# Supply.net
KiCad netlist of a schematic drawn in Altium Designer
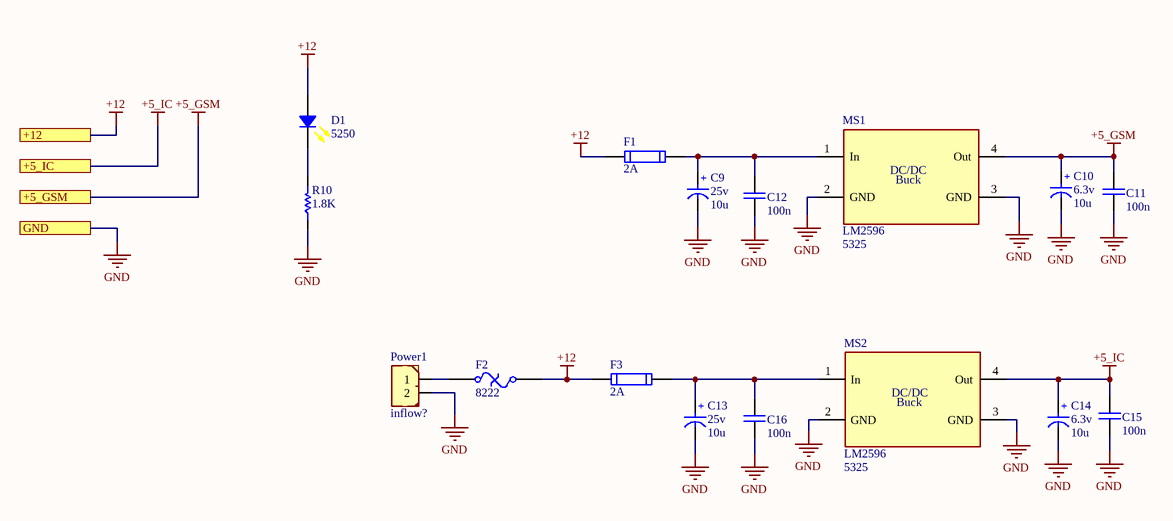
[diagram p0: Supply.SchDoc]

(export (version "E")
  (design (tool "Eeschema 10.0.6"))
  (components
    (comp (ref "C9")
      (value "10u")
      (footprint "SMT_C_Tantalum_B")
      (description "Tantalum Capacitor,TAJ Series-SMD")
      (fields (field (name "RATING") "25v") (field (name "VALIDATION") "Valid"))
      (libsource (lib "aKaReZa") (part "Cap_Tantalum"))
    )
    (comp (ref "C10")
      (value "10u")
      (footprint "SMT_C_Tantalum_B")
      (description "Tantalum Capacitor,TAJ Series-SMD")
      (fields (field (name "RATING") "6.3v") (field (name "VALIDATION") "Valid"))
      (libsource (lib "aKaReZa") (part "Cap_Tantalum"))
    )
    (comp (ref "C11")
      (value "100n")
      (footprint "CAP 1206/3216")
      (description "Bipolar ceramic capacitor SMD")
      (fields (field (name "VALIDATION") "Valid"))
      (libsource (lib "aKaReZa") (part "Cap_Multi_SMD_100nF_1206"))
    )
    (comp (ref "C12")
      (value "100n")
      (footprint "CAP 1206/3216")
      (description "Bipolar ceramic capacitor SMD")
      (fields (field (name "VALIDATION") "Valid"))
      (libsource (lib "aKaReZa") (part "Cap_Multi_SMD_100nF_1206"))
    )
    (comp (ref "C13")
      (value "10u")
      (footprint "SMT_C_Tantalum_B")
      (description "Tantalum Capacitor,TAJ Series-SMD")
      (fields (field (name "RATING") "25v") (field (name "VALIDATION") "Valid"))
      (libsource (lib "aKaReZa") (part "Cap_Tantalum"))
    )
    (comp (ref "C14")
      (value "10u")
      (footprint "SMT_C_Tantalum_B")
      (description "Tantalum Capacitor,TAJ Series-SMD")
      (fields (field (name "RATING") "6.3v") (field (name "VALIDATION") "Valid"))
      (libsource (lib "aKaReZa") (part "Cap_Tantalum"))
    )
    (comp (ref "C15")
      (value "100n")
      (footprint "CAP 1206/3216")
      (description "Bipolar ceramic capacitor SMD")
      (fields (field (name "VALIDATION") "Valid"))
      (libsource (lib "aKaReZa") (part "Cap_Multi_SMD_100nF_1206"))
    )
    (comp (ref "C16")
      (value "100n")
      (footprint "CAP 1206/3216")
      (description "Bipolar ceramic capacitor SMD")
      (fields (field (name "VALIDATION") "Valid"))
      (libsource (lib "aKaReZa") (part "Cap_Multi_SMD_100nF_1206"))
    )
    (comp (ref "D1")
      (value "Yellow, 1206")
      (footprint "LED 1206/3216 YELLOW")
      (description "LED")
      (fields (field (name "INFLOW") "5250") (field (name "VALIDATION") "Valid"))
      (libsource (lib "aKaReZa") (part "Semi_LED_Yellow_1206"))
    )
    (comp (ref "F1")
      (value "2A")
      (footprint "1206_F")
      (description "Short circiut  protection")
      (fields (field (name "VALIDATION") "Valid"))
      (libsource (lib "aKaReZa") (part "Other_Elec_Fuse_SMD"))
    )
    (comp (ref "F2")
      (value "180'C, 10'A")
      (footprint "PIN-W2/E2.8")
      (description "Thermal Fuse")
      (fields (field (name "INFLOW") "8222") (field (name "VALIDATION") "NT"))
      (libsource (lib "aKaReZa") (part "Other_Elec_Fuse_Thermal"))
    )
    (comp (ref "F3")
      (value "2A")
      (footprint "1206_F")
      (description "Short circiut  protection")
      (fields (field (name "VALIDATION") "Valid"))
      (libsource (lib "aKaReZa") (part "Other_Elec_Fuse_SMD"))
    )
    (comp (ref "MS1")
      (value "LM2596")
      (footprint "LM2596_modsen")
      (description "DC to DC Buck converter 1.23V-30V 3A")
      (fields (field (name "INFLOW") "5325") (field (name "VALIDATION") "Valid"))
      (libsource (lib "aKaReZa") (part "ModSen_LM2596"))
    )
    (comp (ref "MS2")
      (value "LM2596")
      (footprint "LM2596_modsen")
      (description "DC to DC Buck converter 1.23V-30V 3A")
      (fields (field (name "INFLOW") "5325") (field (name "VALIDATION") "Valid"))
      (libsource (lib "aKaReZa") (part "ModSen_LM2596"))
    )
    (comp (ref "Power1")
      (value "2'Pin")
      (footprint "Phoenix_2PIN_RA_P5.08mm")
      (description "Power Connector 2'Pin")
      (fields (field (name "INFLOW") "inflow?") (field (name "VALIDATION") "NT"))
      (libsource (lib "aKaReZa") (part "Con_Power_2"))
    )
    (comp (ref "R10")
      (value "1.8K")
      (footprint "RES 1206 (3216X08L)")
      (description "Resistor")
      (fields (field (name "VALIDATION") "Valid"))
      (libsource (lib "aKaReZa") (part "Res_SMD_1206"))
    )
  )
  (nets
    (net (code "1") (name "+5_GSM") (class "Default")
      (node (ref "C10") (pin "1") (pinfunction "+_1") (pintype "passive"))
      (node (ref "C11") (pin "1") (pinfunction "1_1") (pintype "passive"))
      (node (ref "MS1") (pin "4") (pinfunction "Out_4") (pintype "power_in"))
    )
    (net (code "2") (name "+5_IC") (class "Default")
      (node (ref "C14") (pin "1") (pinfunction "+_1") (pintype "passive"))
      (node (ref "C15") (pin "1") (pinfunction "1_1") (pintype "passive"))
      (node (ref "MS2") (pin "4") (pinfunction "Out_4") (pintype "power_in"))
    )
    (net (code "3") (name "+12") (class "Default")
      (node (ref "D1") (pin "1") (pinfunction "1_1") (pintype "passive"))
      (node (ref "F1") (pin "1") (pinfunction "1_1") (pintype "passive"))
      (node (ref "F2") (pin "2") (pinfunction "2_2") (pintype "passive"))
      (node (ref "F3") (pin "1") (pinfunction "1_1") (pintype "passive"))
    )
    (net (code "4") (name "GND") (class "Default")
      (node (ref "C10") (pin "2") (pinfunction "-_2") (pintype "passive"))
      (node (ref "C11") (pin "2") (pinfunction "2_2") (pintype "passive"))
      (node (ref "C12") (pin "2") (pinfunction "2_2") (pintype "passive"))
      (node (ref "C13") (pin "2") (pinfunction "-_2") (pintype "passive"))
      (node (ref "C14") (pin "2") (pinfunction "-_2") (pintype "passive"))
      (node (ref "C15") (pin "2") (pinfunction "2_2") (pintype "passive"))
      (node (ref "C16") (pin "2") (pinfunction "2_2") (pintype "passive"))
      (node (ref "C9") (pin "2") (pinfunction "-_2") (pintype "passive"))
      (node (ref "MS1") (pin "2") (pinfunction "GND_2") (pintype "power_in"))
      (node (ref "MS1") (pin "3") (pinfunction "GND_3") (pintype "power_in"))
      (node (ref "MS2") (pin "2") (pinfunction "GND_2") (pintype "power_in"))
      (node (ref "MS2") (pin "3") (pinfunction "GND_3") (pintype "power_in"))
      (node (ref "Power1") (pin "2") (pinfunction "2_2") (pintype "passive"))
      (node (ref "R10") (pin "1") (pinfunction "1_1") (pintype "passive"))
    )
    (net (code "5") (name "Net-(C9-+)") (class "Default")
      (node (ref "C12") (pin "1") (pinfunction "1_1") (pintype "passive"))
      (node (ref "C9") (pin "1") (pinfunction "+_1") (pintype "passive"))
      (node (ref "F1") (pin "2") (pinfunction "2_2") (pintype "passive"))
      (node (ref "MS1") (pin "1") (pinfunction "In_1") (pintype "power_in"))
    )
    (net (code "6") (name "Net-(C13-+)") (class "Default")
      (node (ref "C13") (pin "1") (pinfunction "+_1") (pintype "passive"))
      (node (ref "C16") (pin "1") (pinfunction "1_1") (pintype "passive"))
      (node (ref "F3") (pin "2") (pinfunction "2_2") (pintype "passive"))
      (node (ref "MS2") (pin "1") (pinfunction "In_1") (pintype "power_in"))
    )
    (net (code "7") (name "Net-(D1-Pad2)") (class "Default")
      (node (ref "D1") (pin "2") (pinfunction "2_2") (pintype "passive"))
      (node (ref "R10") (pin "2") (pinfunction "2_2") (pintype "passive"))
    )
    (net (code "8") (name "Net-(F2-Pad1)") (class "Default")
      (node (ref "F2") (pin "1") (pinfunction "1_1") (pintype "passive"))
      (node (ref "Power1") (pin "1") (pinfunction "1_1") (pintype "passive"))
    )
  )
)
